# PlatLampCon_v1.net
KiCad netlist of a schematic drawn in EAGLE
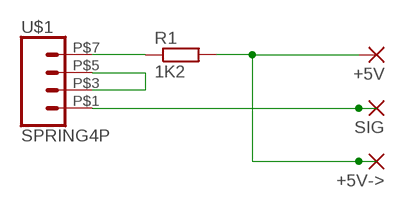
[diagram p0: schematic, sheet 1]

(export (version "E")
  (design (tool "Eeschema 10.0.6"))
  (components
    (comp (ref "+5V")
      (value "2,15/1,0")
      (footprint "eagle-import:2,15_1,0")
      (libsource (lib "eagle-import") (part "2,15/1,0"))
    )
    (comp (ref "+5V->")
      (value "2,15/1,0")
      (footprint "eagle-import:2,15_1,0")
      (libsource (lib "eagle-import") (part "2,15/1,0"))
    )
    (comp (ref "R1")
      (value "1K2")
      (footprint "eagle-import:0207_7")
      (libsource (lib "eagle-import") (part "R-EU_0207/7"))
    )
    (comp (ref "SIG")
      (value "2,15/1,0")
      (footprint "eagle-import:2,15_1,0")
      (libsource (lib "eagle-import") (part "2,15/1,0"))
    )
    (comp (ref "U$1")
      (value "SPRING4P")
      (footprint "eagle-import:SPRING-CON4P")
      (libsource (lib "eagle-import") (part "SPRING4P"))
    )
  )
  (nets
    (net (code "1") (name "Net-(+5V->-P)") (class "Default")
      (node (ref "+5V") (pin "1") (pinfunction "P_1") (pintype "passive"))
      (node (ref "+5V->") (pin "1") (pinfunction "P_1") (pintype "passive"))
      (node (ref "R1") (pin "2") (pinfunction "2_2") (pintype "passive"))
    )
    (net (code "2") (name "Net-(SIG-P)") (class "Default")
      (node (ref "SIG") (pin "1") (pinfunction "P_1") (pintype "passive"))
      (node (ref "U$1") (pin "P$1") (pinfunction "1_P$1") (pintype "passive"))
    )
    (net (code "3") (name "Net-(U$1-2)") (class "Default")
      (node (ref "U$1") (pin "P$3") (pinfunction "2_P$3") (pintype "passive"))
      (node (ref "U$1") (pin "P$5") (pinfunction "3_P$5") (pintype "passive"))
    )
    (net (code "4") (name "Net-(U$1-4)") (class "Default")
      (node (ref "R1") (pin "1") (pinfunction "1_1") (pintype "passive"))
      (node (ref "U$1") (pin "P$7") (pinfunction "4_P$7") (pintype "passive"))
    )
  )
)
